# Adafruit_bicolor_bargraph_24.net
KiCad netlist of a schematic drawn in EAGLE
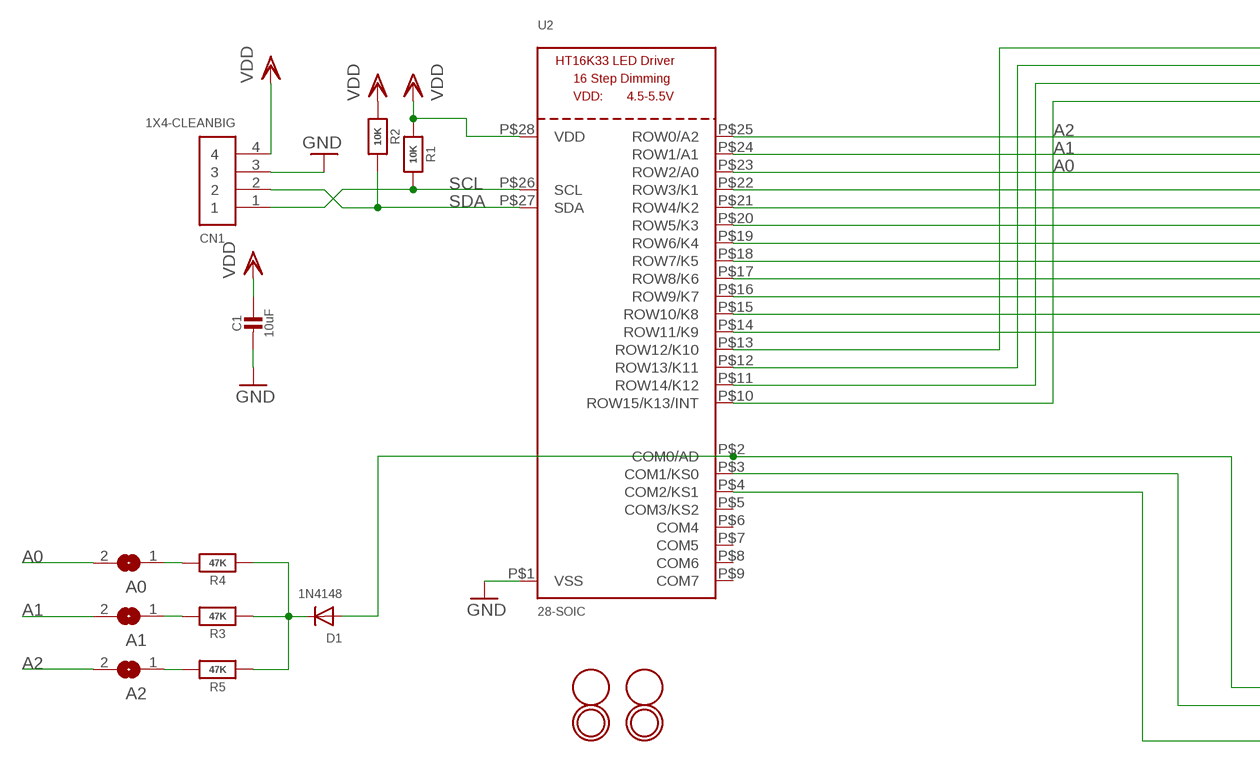
[diagram p0: schematic, sheet 1, part 1 of 2]
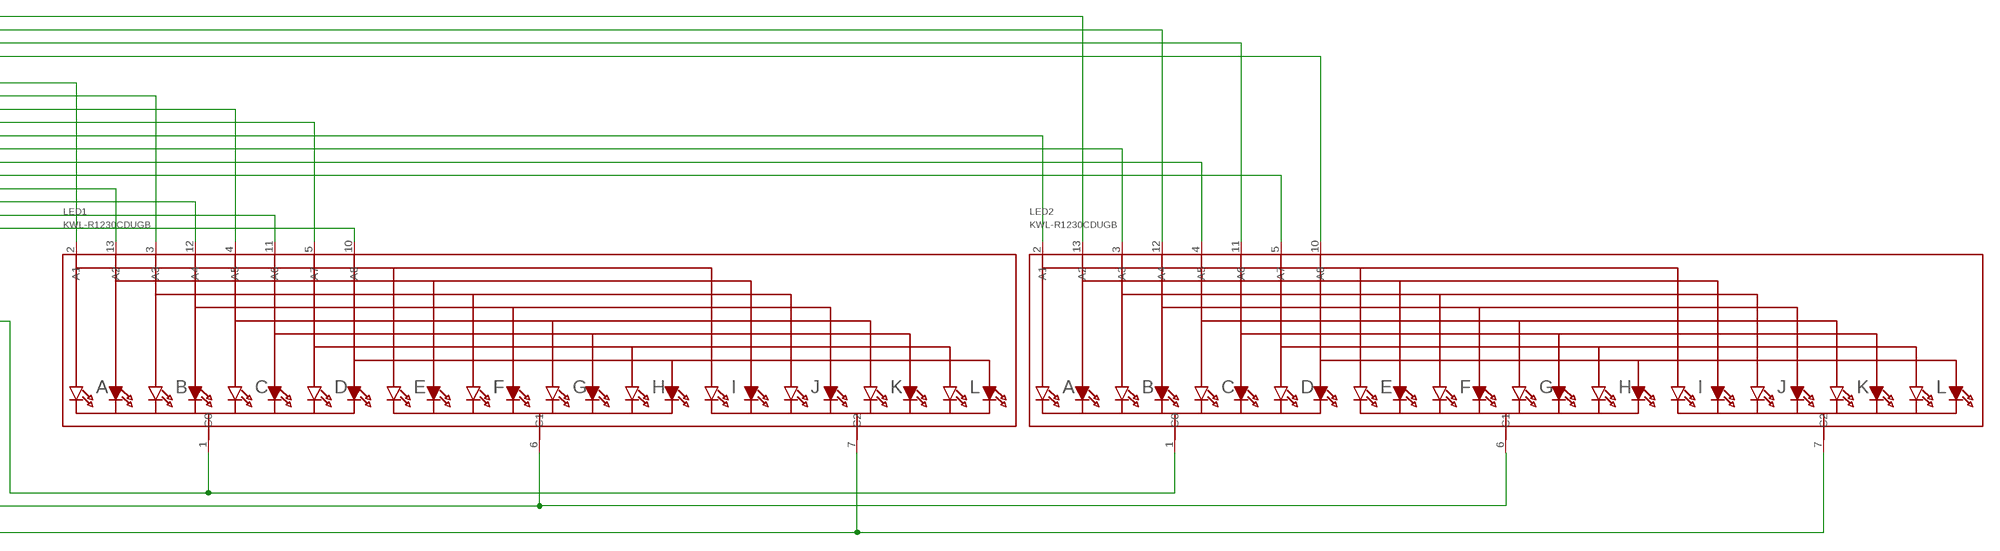
[diagram p1: schematic, sheet 1, part 2 of 2]

(export (version "E")
  (design (tool "Eeschema 10.0.6"))
  (components
    (comp (ref "A0")
      (value "SOLDERJUMPERREFLOW_NOPASTE")
      (footprint "eagle-import:SOLDERJUMPER_REFLOW_NOPASTE")
      (libsource (lib "eagle-import") (part "SOLDERJUMPERREFLOW_NOPASTE"))
    )
    (comp (ref "A1")
      (value "SOLDERJUMPERREFLOW_NOPASTE")
      (footprint "eagle-import:SOLDERJUMPER_REFLOW_NOPASTE")
      (libsource (lib "eagle-import") (part "SOLDERJUMPERREFLOW_NOPASTE"))
    )
    (comp (ref "A2")
      (value "SOLDERJUMPERREFLOW_NOPASTE")
      (footprint "eagle-import:SOLDERJUMPER_REFLOW_NOPASTE")
      (libsource (lib "eagle-import") (part "SOLDERJUMPERREFLOW_NOPASTE"))
    )
    (comp (ref "C1")
      (value "10uF")
      (footprint "eagle-import:0805-NO")
      (libsource (lib "eagle-import") (part "CAP_CERAMIC0805-NOOUTLINE"))
    )
    (comp (ref "CN1")
      (value "1X4-CLEANBIG")
      (footprint "eagle-import:1X04-CLEANBIG")
      (libsource (lib "eagle-import") (part "1X4-CLEANBIG"))
    )
    (comp (ref "D1")
      (value "1N4148")
      (footprint "eagle-import:SOD-323F")
      (libsource (lib "eagle-import") (part "DIODESOD-323F"))
    )
    (comp (ref "LED1")
      (value "KWL-R1230CDUGB")
      (footprint "eagle-import:SEGMENT_BICOL_BL-AR12Z3010")
      (libsource (lib "eagle-import") (part "KWL-R1230CDUGB"))
    )
    (comp (ref "LED2")
      (value "KWL-R1230CDUGB")
      (footprint "eagle-import:SEGMENT_BICOL_BL-AR12Z3010")
      (libsource (lib "eagle-import") (part "KWL-R1230CDUGB"))
    )
    (comp (ref "R1")
      (value "10K")
      (footprint "eagle-import:0805-NO")
      (libsource (lib "eagle-import") (part "RESISTOR0805_NOOUTLINE"))
    )
    (comp (ref "R2")
      (value "10K")
      (footprint "eagle-import:0805-NO")
      (libsource (lib "eagle-import") (part "RESISTOR0805_NOOUTLINE"))
    )
    (comp (ref "R3")
      (value "47K")
      (footprint "eagle-import:0805-NO")
      (libsource (lib "eagle-import") (part "RESISTOR0805_NOOUTLINE"))
    )
    (comp (ref "R4")
      (value "47K")
      (footprint "eagle-import:0805-NO")
      (libsource (lib "eagle-import") (part "RESISTOR0805_NOOUTLINE"))
    )
    (comp (ref "R5")
      (value "47K")
      (footprint "eagle-import:0805-NO")
      (libsource (lib "eagle-import") (part "RESISTOR0805_NOOUTLINE"))
    )
    (comp (ref "U$1")
      (value "FIDUCIAL")
      (footprint "eagle-import:FIDUCIAL_1MM")
      (libsource (lib "eagle-import") (part "FIDUCIAL"))
    )
    (comp (ref "U$2")
      (value "FIDUCIAL")
      (footprint "eagle-import:FIDUCIAL_1MM")
      (libsource (lib "eagle-import") (part "FIDUCIAL"))
    )
    (comp (ref "U$3")
      (value "MOUNTINGHOLE2.5")
      (footprint "eagle-import:MOUNTINGHOLE_2.5_PLATED")
      (libsource (lib "eagle-import") (part "MOUNTINGHOLE2.5"))
    )
    (comp (ref "U$4")
      (value "MOUNTINGHOLE2.5")
      (footprint "eagle-import:MOUNTINGHOLE_2.5_PLATED")
      (libsource (lib "eagle-import") (part "MOUNTINGHOLE2.5"))
    )
    (comp (ref "U2")
      (value "28-SOIC")
      (footprint "eagle-import:SOP28_300MIL")
      (libsource (lib "eagle-import") (part "HT16K33_SOP28"))
    )
  )
  (nets
    (net (code "1") (name "/A0") (class "Default")
      (node (ref "A0") (pin "2") (pinfunction "2_2") (pintype "passive"))
      (node (ref "LED1") (pin "4") (pinfunction "A5_4") (pintype "bidirectional"))
      (node (ref "U2") (pin "P$23") (pinfunction "ROW2/A0_P$23") (pintype "bidirectional"))
    )
    (net (code "2") (name "/A1") (class "Default")
      (node (ref "A1") (pin "2") (pinfunction "2_2") (pintype "passive"))
      (node (ref "LED1") (pin "3") (pinfunction "A3_3") (pintype "bidirectional"))
      (node (ref "U2") (pin "P$24") (pinfunction "ROW1/A1_P$24") (pintype "bidirectional"))
    )
    (net (code "3") (name "/A2") (class "Default")
      (node (ref "A2") (pin "2") (pinfunction "2_2") (pintype "passive"))
      (node (ref "LED1") (pin "2") (pinfunction "A1_2") (pintype "bidirectional"))
      (node (ref "U2") (pin "P$25") (pinfunction "ROW0/A2_P$25") (pintype "bidirectional"))
    )
    (net (code "4") (name "/SCL") (class "Default")
      (node (ref "CN1") (pin "1") (pinfunction "1_1") (pintype "bidirectional"))
      (node (ref "R1") (pin "2") (pinfunction "2_2") (pintype "passive"))
      (node (ref "U2") (pin "P$26") (pinfunction "SCL_P$26") (pintype "bidirectional"))
    )
    (net (code "5") (name "/SDA") (class "Default")
      (node (ref "CN1") (pin "2") (pinfunction "2_2") (pintype "bidirectional"))
      (node (ref "R2") (pin "2") (pinfunction "2_2") (pintype "passive"))
      (node (ref "U2") (pin "P$27") (pinfunction "SDA_P$27") (pintype "bidirectional"))
    )
    (net (code "6") (name "GND") (class "Default")
      (node (ref "C1") (pin "2") (pinfunction "2_2") (pintype "passive"))
      (node (ref "CN1") (pin "3") (pinfunction "3_3") (pintype "bidirectional"))
      (node (ref "U2") (pin "P$1") (pinfunction "VSS_P$1") (pintype "bidirectional"))
    )
    (net (code "7") (name "Net-(A0-Pad1)") (class "Default")
      (node (ref "A0") (pin "1") (pinfunction "1_1") (pintype "passive"))
      (node (ref "R4") (pin "2") (pinfunction "2_2") (pintype "passive"))
    )
    (net (code "8") (name "Net-(A1-Pad1)") (class "Default")
      (node (ref "A1") (pin "1") (pinfunction "1_1") (pintype "passive"))
      (node (ref "R3") (pin "2") (pinfunction "2_2") (pintype "passive"))
    )
    (net (code "9") (name "Net-(A2-Pad1)") (class "Default")
      (node (ref "A2") (pin "1") (pinfunction "1_1") (pintype "passive"))
      (node (ref "R5") (pin "2") (pinfunction "2_2") (pintype "passive"))
    )
    (net (code "10") (name "Net-(D1-PadC)") (class "Default")
      (node (ref "D1") (pin "C") (pinfunction "C_C") (pintype "passive"))
      (node (ref "R3") (pin "1") (pinfunction "1_1") (pintype "passive"))
      (node (ref "R4") (pin "1") (pinfunction "1_1") (pintype "passive"))
      (node (ref "R5") (pin "1") (pinfunction "1_1") (pintype "passive"))
    )
    (net (code "11") (name "Net-(LED1-A2)") (class "Default")
      (node (ref "LED1") (pin "13") (pinfunction "A2_13") (pintype "bidirectional"))
      (node (ref "U2") (pin "P$17") (pinfunction "ROW8/K6_P$17") (pintype "bidirectional"))
    )
    (net (code "12") (name "Net-(LED1-A4)") (class "Default")
      (node (ref "LED1") (pin "12") (pinfunction "A4_12") (pintype "bidirectional"))
      (node (ref "U2") (pin "P$16") (pinfunction "ROW9/K7_P$16") (pintype "bidirectional"))
    )
    (net (code "13") (name "Net-(LED1-A6)") (class "Default")
      (node (ref "LED1") (pin "11") (pinfunction "A6_11") (pintype "bidirectional"))
      (node (ref "U2") (pin "P$15") (pinfunction "ROW10/K8_P$15") (pintype "bidirectional"))
    )
    (net (code "14") (name "Net-(LED1-A7)") (class "Default")
      (node (ref "LED1") (pin "5") (pinfunction "A7_5") (pintype "bidirectional"))
      (node (ref "U2") (pin "P$22") (pinfunction "ROW3/K1_P$22") (pintype "bidirectional"))
    )
    (net (code "15") (name "Net-(LED1-A8)") (class "Default")
      (node (ref "LED1") (pin "10") (pinfunction "A8_10") (pintype "bidirectional"))
      (node (ref "U2") (pin "P$14") (pinfunction "ROW11/K9_P$14") (pintype "bidirectional"))
    )
    (net (code "16") (name "Net-(LED1-C0)") (class "Default")
      (node (ref "D1") (pin "A") (pinfunction "A_A") (pintype "passive"))
      (node (ref "LED1") (pin "1") (pinfunction "C0_1") (pintype "bidirectional"))
      (node (ref "LED2") (pin "1") (pinfunction "C0_1") (pintype "bidirectional"))
      (node (ref "U2") (pin "P$2") (pinfunction "COM0/AD_P$2") (pintype "bidirectional"))
    )
    (net (code "17") (name "Net-(LED1-C1)") (class "Default")
      (node (ref "LED1") (pin "6") (pinfunction "C1_6") (pintype "bidirectional"))
      (node (ref "LED2") (pin "6") (pinfunction "C1_6") (pintype "bidirectional"))
      (node (ref "U2") (pin "P$3") (pinfunction "COM1/KS0_P$3") (pintype "bidirectional"))
    )
    (net (code "18") (name "Net-(LED1-C2)") (class "Default")
      (node (ref "LED1") (pin "7") (pinfunction "C2_7") (pintype "bidirectional"))
      (node (ref "LED2") (pin "7") (pinfunction "C2_7") (pintype "bidirectional"))
      (node (ref "U2") (pin "P$4") (pinfunction "COM2/KS1_P$4") (pintype "bidirectional"))
    )
    (net (code "19") (name "Net-(LED2-A1)") (class "Default")
      (node (ref "LED2") (pin "2") (pinfunction "A1_2") (pintype "bidirectional"))
      (node (ref "U2") (pin "P$21") (pinfunction "ROW4/K2_P$21") (pintype "bidirectional"))
    )
    (net (code "20") (name "Net-(LED2-A2)") (class "Default")
      (node (ref "LED2") (pin "13") (pinfunction "A2_13") (pintype "bidirectional"))
      (node (ref "U2") (pin "P$13") (pinfunction "ROW12/K10_P$13") (pintype "bidirectional"))
    )
    (net (code "21") (name "Net-(LED2-A3)") (class "Default")
      (node (ref "LED2") (pin "3") (pinfunction "A3_3") (pintype "bidirectional"))
      (node (ref "U2") (pin "P$20") (pinfunction "ROW5/K3_P$20") (pintype "bidirectional"))
    )
    (net (code "22") (name "Net-(LED2-A4)") (class "Default")
      (node (ref "LED2") (pin "12") (pinfunction "A4_12") (pintype "bidirectional"))
      (node (ref "U2") (pin "P$12") (pinfunction "ROW13/K11_P$12") (pintype "bidirectional"))
    )
    (net (code "23") (name "Net-(LED2-A5)") (class "Default")
      (node (ref "LED2") (pin "4") (pinfunction "A5_4") (pintype "bidirectional"))
      (node (ref "U2") (pin "P$19") (pinfunction "ROW6/K4_P$19") (pintype "bidirectional"))
    )
    (net (code "24") (name "Net-(LED2-A6)") (class "Default")
      (node (ref "LED2") (pin "11") (pinfunction "A6_11") (pintype "bidirectional"))
      (node (ref "U2") (pin "P$11") (pinfunction "ROW14/K12_P$11") (pintype "bidirectional"))
    )
    (net (code "25") (name "Net-(LED2-A7)") (class "Default")
      (node (ref "LED2") (pin "5") (pinfunction "A7_5") (pintype "bidirectional"))
      (node (ref "U2") (pin "P$18") (pinfunction "ROW7/K5_P$18") (pintype "bidirectional"))
    )
    (net (code "26") (name "Net-(LED2-A8)") (class "Default")
      (node (ref "LED2") (pin "10") (pinfunction "A8_10") (pintype "bidirectional"))
      (node (ref "U2") (pin "P$10") (pinfunction "ROW15/K13/INT_P$10") (pintype "bidirectional"))
    )
    (net (code "27") (name "VDD") (class "Default")
      (node (ref "C1") (pin "1") (pinfunction "1_1") (pintype "passive"))
      (node (ref "CN1") (pin "4") (pinfunction "4_4") (pintype "bidirectional"))
      (node (ref "R1") (pin "1") (pinfunction "1_1") (pintype "passive"))
      (node (ref "R2") (pin "1") (pinfunction "1_1") (pintype "passive"))
      (node (ref "U2") (pin "P$28") (pinfunction "VDD_P$28") (pintype "bidirectional"))
    )
    (net (code "28") (name "unconnected-(U2-COM3{slash}KS2-PadP$5)") (class "Default")
      (node (ref "U2") (pin "P$5") (pinfunction "COM3/KS2_P$5") (pintype "bidirectional"))
    )
    (net (code "29") (name "unconnected-(U2-COM4-PadP$6)") (class "Default")
      (node (ref "U2") (pin "P$6") (pinfunction "COM4_P$6") (pintype "bidirectional"))
    )
    (net (code "30") (name "unconnected-(U2-COM5-PadP$7)") (class "Default")
      (node (ref "U2") (pin "P$7") (pinfunction "COM5_P$7") (pintype "bidirectional"))
    )
    (net (code "31") (name "unconnected-(U2-COM6-PadP$8)") (class "Default")
      (node (ref "U2") (pin "P$8") (pinfunction "COM6_P$8") (pintype "bidirectional"))
    )
    (net (code "32") (name "unconnected-(U2-COM7-PadP$9)") (class "Default")
      (node (ref "U2") (pin "P$9") (pinfunction "COM7_P$9") (pintype "bidirectional"))
    )
  )
)
